# Gate_Drivers.net
KiCad netlist of a schematic drawn in Altium Designer
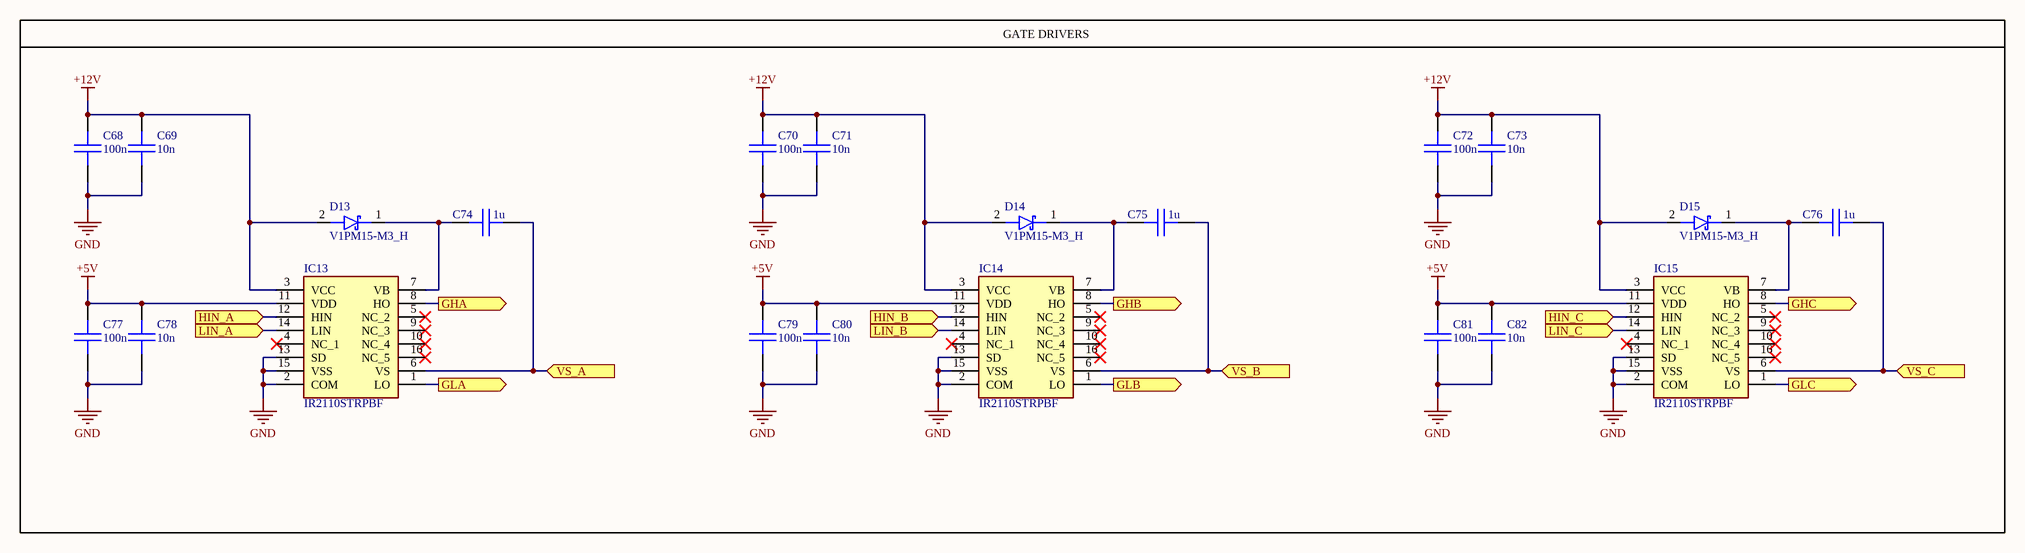
[diagram p0: Gate_Drivers.SchDoc]

(export (version "E")
  (design (tool "Eeschema 10.0.6"))
  (components
    (comp (ref "C68")
      (value "100n")
      (footprint "C_0603")
      (description "SMD Chip Capacitor")
      (libsource (lib "My_Integrated_Lib") (part "CAP"))
    )
    (comp (ref "C69")
      (value "10n")
      (footprint "C_0603")
      (description "SMD Chip Capacitor")
      (libsource (lib "My_Integrated_Lib") (part "CAP"))
    )
    (comp (ref "C70")
      (value "100n")
      (footprint "C_0603")
      (description "SMD Chip Capacitor")
      (libsource (lib "My_Integrated_Lib") (part "CAP"))
    )
    (comp (ref "C71")
      (value "10n")
      (footprint "C_0603")
      (description "SMD Chip Capacitor")
      (libsource (lib "My_Integrated_Lib") (part "CAP"))
    )
    (comp (ref "C72")
      (value "100n")
      (footprint "C_0603")
      (description "SMD Chip Capacitor")
      (libsource (lib "My_Integrated_Lib") (part "CAP"))
    )
    (comp (ref "C73")
      (value "10n")
      (footprint "C_0603")
      (description "SMD Chip Capacitor")
      (libsource (lib "My_Integrated_Lib") (part "CAP"))
    )
    (comp (ref "C74")
      (value "1u")
      (footprint "C_0805")
      (description "SMD Chip Capacitor")
      (libsource (lib "My_Integrated_Lib") (part "CAP"))
    )
    (comp (ref "C75")
      (value "1u")
      (footprint "C_0805")
      (description "SMD Chip Capacitor")
      (libsource (lib "My_Integrated_Lib") (part "CAP"))
    )
    (comp (ref "C76")
      (value "1u")
      (footprint "C_0805")
      (description "SMD Chip Capacitor")
      (libsource (lib "My_Integrated_Lib") (part "CAP"))
    )
    (comp (ref "C77")
      (value "100n")
      (footprint "C_0603")
      (description "SMD Chip Capacitor")
      (libsource (lib "My_Integrated_Lib") (part "CAP"))
    )
    (comp (ref "C78")
      (value "10n")
      (footprint "C_0603")
      (description "SMD Chip Capacitor")
      (libsource (lib "My_Integrated_Lib") (part "CAP"))
    )
    (comp (ref "C79")
      (value "100n")
      (footprint "C_0603")
      (description "SMD Chip Capacitor")
      (libsource (lib "My_Integrated_Lib") (part "CAP"))
    )
    (comp (ref "C80")
      (value "10n")
      (footprint "C_0603")
      (description "SMD Chip Capacitor")
      (libsource (lib "My_Integrated_Lib") (part "CAP"))
    )
    (comp (ref "C81")
      (value "100n")
      (footprint "C_0603")
      (description "SMD Chip Capacitor")
      (libsource (lib "My_Integrated_Lib") (part "CAP"))
    )
    (comp (ref "C82")
      (value "10n")
      (footprint "C_0603")
      (description "SMD Chip Capacitor")
      (libsource (lib "My_Integrated_Lib") (part "CAP"))
    )
    (comp (ref "D13")
      (value "V1PM15-M3_H")
      (footprint "DO-219AD-2")
      (description "Schottky Diode, 150V, 1A, Vf: 1.13V")
      (libsource (lib "My_Integrated_Lib") (part "DIODE_SCHOTTKY_V1PM15-M3_H"))
    )
    (comp (ref "D14")
      (value "V1PM15-M3_H")
      (footprint "DO-219AD-2")
      (description "Schottky Diode, 150V, 1A, Vf: 1.13V")
      (libsource (lib "My_Integrated_Lib") (part "DIODE_SCHOTTKY_V1PM15-M3_H"))
    )
    (comp (ref "D15")
      (value "V1PM15-M3_H")
      (footprint "DO-219AD-2")
      (description "Schottky Diode, 150V, 1A, Vf: 1.13V")
      (libsource (lib "My_Integrated_Lib") (part "DIODE_SCHOTTKY_V1PM15-M3_H"))
    )
    (comp (ref "IC13")
      (value "IR2110STRPBF")
      (footprint "SOIC127P1032X265-16N")
      (description "Integrated Circuit")
      (fields (field (name "MOUSER PART NUMBER") "942-IR2110STRPBF"))
      (libsource (lib "My_Integrated_Lib") (part "IR2110STRPBF"))
    )
    (comp (ref "IC14")
      (value "IR2110STRPBF")
      (footprint "SOIC127P1032X265-16N")
      (description "Integrated Circuit")
      (fields (field (name "MOUSER PART NUMBER") "942-IR2110STRPBF"))
      (libsource (lib "My_Integrated_Lib") (part "IR2110STRPBF"))
    )
    (comp (ref "IC15")
      (value "IR2110STRPBF")
      (footprint "SOIC127P1032X265-16N")
      (description "Integrated Circuit")
      (fields (field (name "MOUSER PART NUMBER") "942-IR2110STRPBF"))
      (libsource (lib "My_Integrated_Lib") (part "IR2110STRPBF"))
    )
  )
  (nets
    (net (code "1") (name "+5V") (class "Default")
      (node (ref "C77") (pin "2") (pinfunction "2_2") (pintype "passive"))
      (node (ref "C78") (pin "2") (pinfunction "2_2") (pintype "passive"))
      (node (ref "C79") (pin "2") (pinfunction "2_2") (pintype "passive"))
      (node (ref "C80") (pin "2") (pinfunction "2_2") (pintype "passive"))
      (node (ref "C81") (pin "2") (pinfunction "2_2") (pintype "passive"))
      (node (ref "C82") (pin "2") (pinfunction "2_2") (pintype "passive"))
      (node (ref "IC13") (pin "11") (pinfunction "VDD_11") (pintype "passive"))
      (node (ref "IC14") (pin "11") (pinfunction "VDD_11") (pintype "passive"))
      (node (ref "IC15") (pin "11") (pinfunction "VDD_11") (pintype "passive"))
    )
    (net (code "2") (name "+12V") (class "Default")
      (node (ref "C68") (pin "2") (pinfunction "2_2") (pintype "passive"))
      (node (ref "C69") (pin "2") (pinfunction "2_2") (pintype "passive"))
      (node (ref "C70") (pin "2") (pinfunction "2_2") (pintype "passive"))
      (node (ref "C71") (pin "2") (pinfunction "2_2") (pintype "passive"))
      (node (ref "C72") (pin "2") (pinfunction "2_2") (pintype "passive"))
      (node (ref "C73") (pin "2") (pinfunction "2_2") (pintype "passive"))
      (node (ref "D13") (pin "2") (pinfunction "A_2") (pintype "passive"))
      (node (ref "D14") (pin "2") (pinfunction "A_2") (pintype "passive"))
      (node (ref "D15") (pin "2") (pinfunction "A_2") (pintype "passive"))
      (node (ref "IC13") (pin "3") (pinfunction "VCC_3") (pintype "passive"))
      (node (ref "IC14") (pin "3") (pinfunction "VCC_3") (pintype "passive"))
      (node (ref "IC15") (pin "3") (pinfunction "VCC_3") (pintype "passive"))
    )
    (net (code "3") (name "/GHA") (class "Default")
      (node (ref "IC13") (pin "8") (pinfunction "HO_8") (pintype "passive"))
    )
    (net (code "4") (name "/GHB") (class "Default")
      (node (ref "IC14") (pin "8") (pinfunction "HO_8") (pintype "passive"))
    )
    (net (code "5") (name "/GHC") (class "Default")
      (node (ref "IC15") (pin "8") (pinfunction "HO_8") (pintype "passive"))
    )
    (net (code "6") (name "/GLA") (class "Default")
      (node (ref "IC13") (pin "1") (pinfunction "LO_1") (pintype "passive"))
    )
    (net (code "7") (name "/GLB") (class "Default")
      (node (ref "IC14") (pin "1") (pinfunction "LO_1") (pintype "passive"))
    )
    (net (code "8") (name "/GLC") (class "Default")
      (node (ref "IC15") (pin "1") (pinfunction "LO_1") (pintype "passive"))
    )
    (net (code "9") (name "/HIN_A") (class "Default")
      (node (ref "IC13") (pin "12") (pinfunction "HIN_12") (pintype "passive"))
    )
    (net (code "10") (name "/HIN_B") (class "Default")
      (node (ref "IC14") (pin "12") (pinfunction "HIN_12") (pintype "passive"))
    )
    (net (code "11") (name "/HIN_C") (class "Default")
      (node (ref "IC15") (pin "12") (pinfunction "HIN_12") (pintype "passive"))
    )
    (net (code "12") (name "/LIN_A") (class "Default")
      (node (ref "IC13") (pin "14") (pinfunction "LIN_14") (pintype "passive"))
    )
    (net (code "13") (name "/LIN_B") (class "Default")
      (node (ref "IC14") (pin "14") (pinfunction "LIN_14") (pintype "passive"))
    )
    (net (code "14") (name "/LIN_C") (class "Default")
      (node (ref "IC15") (pin "14") (pinfunction "LIN_14") (pintype "passive"))
    )
    (net (code "15") (name "/VS_A") (class "Default")
      (node (ref "C74") (pin "1") (pinfunction "1_1") (pintype "passive"))
      (node (ref "IC13") (pin "6") (pinfunction "VS_6") (pintype "passive"))
    )
    (net (code "16") (name "/VS_B") (class "Default")
      (node (ref "C75") (pin "1") (pinfunction "1_1") (pintype "passive"))
      (node (ref "IC14") (pin "6") (pinfunction "VS_6") (pintype "passive"))
    )
    (net (code "17") (name "/VS_C") (class "Default")
      (node (ref "C76") (pin "1") (pinfunction "1_1") (pintype "passive"))
      (node (ref "IC15") (pin "6") (pinfunction "VS_6") (pintype "passive"))
    )
    (net (code "18") (name "GND") (class "Default")
      (node (ref "C68") (pin "1") (pinfunction "1_1") (pintype "passive"))
      (node (ref "C69") (pin "1") (pinfunction "1_1") (pintype "passive"))
      (node (ref "C70") (pin "1") (pinfunction "1_1") (pintype "passive"))
      (node (ref "C71") (pin "1") (pinfunction "1_1") (pintype "passive"))
      (node (ref "C72") (pin "1") (pinfunction "1_1") (pintype "passive"))
      (node (ref "C73") (pin "1") (pinfunction "1_1") (pintype "passive"))
      (node (ref "C77") (pin "1") (pinfunction "1_1") (pintype "passive"))
      (node (ref "C78") (pin "1") (pinfunction "1_1") (pintype "passive"))
      (node (ref "C79") (pin "1") (pinfunction "1_1") (pintype "passive"))
      (node (ref "C80") (pin "1") (pinfunction "1_1") (pintype "passive"))
      (node (ref "C81") (pin "1") (pinfunction "1_1") (pintype "passive"))
      (node (ref "C82") (pin "1") (pinfunction "1_1") (pintype "passive"))
      (node (ref "IC13") (pin "13") (pinfunction "SD_13") (pintype "passive"))
      (node (ref "IC13") (pin "15") (pinfunction "VSS_15") (pintype "passive"))
      (node (ref "IC13") (pin "2") (pinfunction "COM_2") (pintype "passive"))
      (node (ref "IC14") (pin "13") (pinfunction "SD_13") (pintype "passive"))
      (node (ref "IC14") (pin "15") (pinfunction "VSS_15") (pintype "passive"))
      (node (ref "IC14") (pin "2") (pinfunction "COM_2") (pintype "passive"))
      (node (ref "IC15") (pin "13") (pinfunction "SD_13") (pintype "passive"))
      (node (ref "IC15") (pin "15") (pinfunction "VSS_15") (pintype "passive"))
      (node (ref "IC15") (pin "2") (pinfunction "COM_2") (pintype "passive"))
    )
    (net (code "19") (name "Net-(D13-K)") (class "Default")
      (node (ref "C74") (pin "2") (pinfunction "2_2") (pintype "passive"))
      (node (ref "D13") (pin "1") (pinfunction "K_1") (pintype "passive"))
      (node (ref "IC13") (pin "7") (pinfunction "VB_7") (pintype "passive"))
    )
    (net (code "20") (name "Net-(D14-K)") (class "Default")
      (node (ref "C75") (pin "2") (pinfunction "2_2") (pintype "passive"))
      (node (ref "D14") (pin "1") (pinfunction "K_1") (pintype "passive"))
      (node (ref "IC14") (pin "7") (pinfunction "VB_7") (pintype "passive"))
    )
    (net (code "21") (name "Net-(D15-K)") (class "Default")
      (node (ref "C76") (pin "2") (pinfunction "2_2") (pintype "passive"))
      (node (ref "D15") (pin "1") (pinfunction "K_1") (pintype "passive"))
      (node (ref "IC15") (pin "7") (pinfunction "VB_7") (pintype "passive"))
    )
    (net (code "22") (name "unconnected-(IC13-NC_1-Pad4)") (class "Default")
      (node (ref "IC13") (pin "4") (pinfunction "NC_1_4") (pintype "passive+no_connect"))
    )
    (net (code "23") (name "unconnected-(IC13-NC_2-Pad5)") (class "Default")
      (node (ref "IC13") (pin "5") (pinfunction "NC_2_5") (pintype "passive+no_connect"))
    )
    (net (code "24") (name "unconnected-(IC13-NC_3-Pad9)") (class "Default")
      (node (ref "IC13") (pin "9") (pinfunction "NC_3_9") (pintype "passive+no_connect"))
    )
    (net (code "25") (name "unconnected-(IC13-NC_4-Pad10)") (class "Default")
      (node (ref "IC13") (pin "10") (pinfunction "NC_4_10") (pintype "passive+no_connect"))
    )
    (net (code "26") (name "unconnected-(IC13-NC_5-Pad16)") (class "Default")
      (node (ref "IC13") (pin "16") (pinfunction "NC_5_16") (pintype "passive+no_connect"))
    )
    (net (code "27") (name "unconnected-(IC14-NC_1-Pad4)") (class "Default")
      (node (ref "IC14") (pin "4") (pinfunction "NC_1_4") (pintype "passive+no_connect"))
    )
    (net (code "28") (name "unconnected-(IC14-NC_2-Pad5)") (class "Default")
      (node (ref "IC14") (pin "5") (pinfunction "NC_2_5") (pintype "passive+no_connect"))
    )
    (net (code "29") (name "unconnected-(IC14-NC_3-Pad9)") (class "Default")
      (node (ref "IC14") (pin "9") (pinfunction "NC_3_9") (pintype "passive+no_connect"))
    )
    (net (code "30") (name "unconnected-(IC14-NC_4-Pad10)") (class "Default")
      (node (ref "IC14") (pin "10") (pinfunction "NC_4_10") (pintype "passive+no_connect"))
    )
    (net (code "31") (name "unconnected-(IC14-NC_5-Pad16)") (class "Default")
      (node (ref "IC14") (pin "16") (pinfunction "NC_5_16") (pintype "passive+no_connect"))
    )
    (net (code "32") (name "unconnected-(IC15-NC_1-Pad4)") (class "Default")
      (node (ref "IC15") (pin "4") (pinfunction "NC_1_4") (pintype "passive+no_connect"))
    )
    (net (code "33") (name "unconnected-(IC15-NC_2-Pad5)") (class "Default")
      (node (ref "IC15") (pin "5") (pinfunction "NC_2_5") (pintype "passive+no_connect"))
    )
    (net (code "34") (name "unconnected-(IC15-NC_3-Pad9)") (class "Default")
      (node (ref "IC15") (pin "9") (pinfunction "NC_3_9") (pintype "passive+no_connect"))
    )
    (net (code "35") (name "unconnected-(IC15-NC_4-Pad10)") (class "Default")
      (node (ref "IC15") (pin "10") (pinfunction "NC_4_10") (pintype "passive+no_connect"))
    )
    (net (code "36") (name "unconnected-(IC15-NC_5-Pad16)") (class "Default")
      (node (ref "IC15") (pin "16") (pinfunction "NC_5_16") (pintype "passive+no_connect"))
    )
  )
)
